# DMB-4770-4-Analog_4-DAC.net
KiCad netlist of a schematic drawn in EAGLE
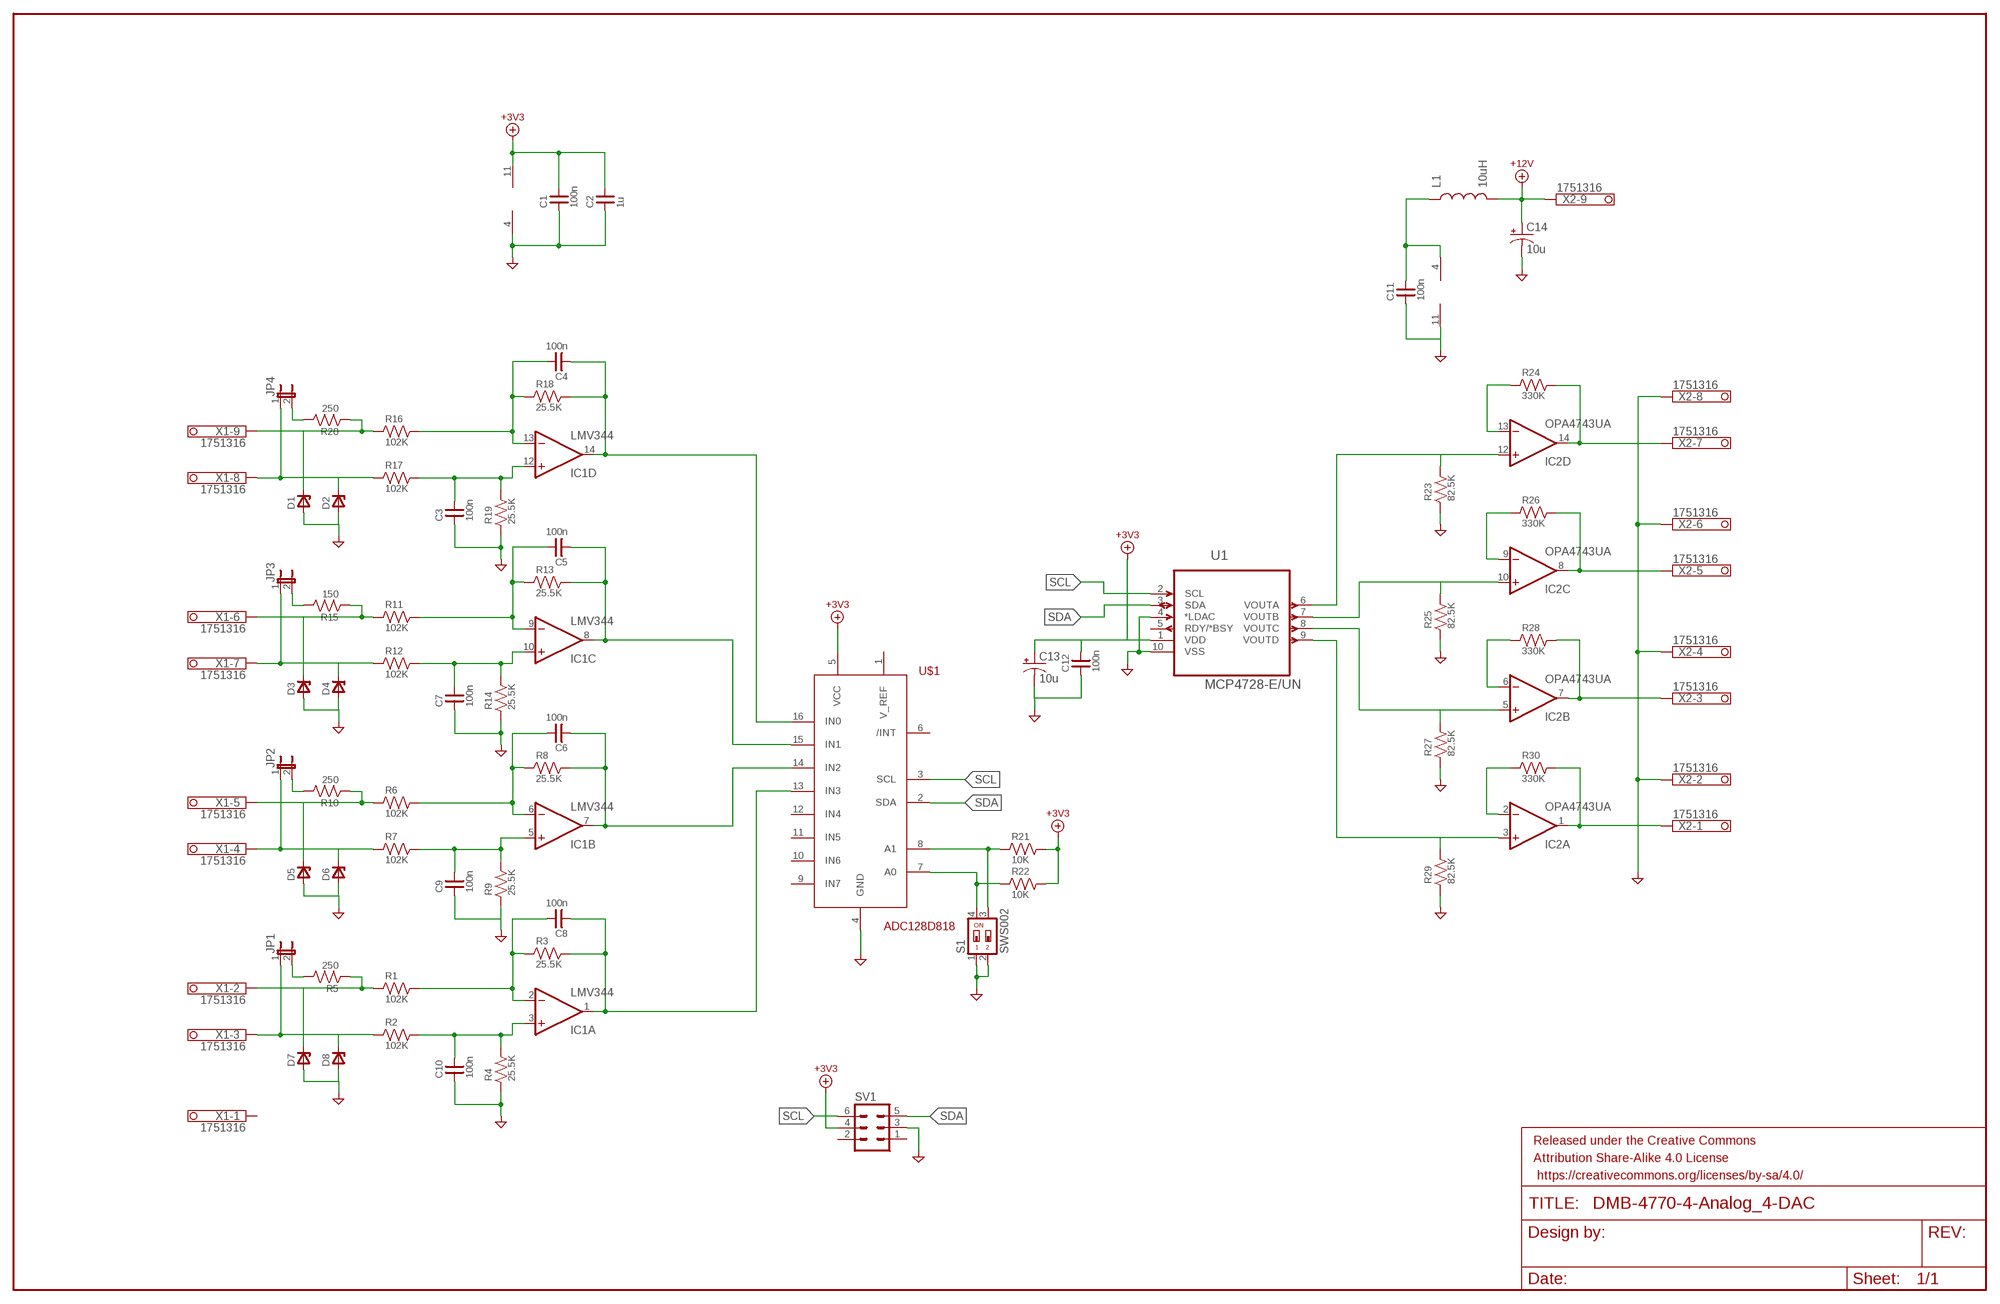
[diagram p0: schematic, sheet 1]

(export (version "E")
  (design (tool "Eeschema 10.0.6"))
  (components
    (comp (ref "C1")
      (value "100n")
      (footprint "eagle-import:C0805")
      (libsource (lib "eagle-import") (part "C0805"))
    )
    (comp (ref "C2")
      (value "1u")
      (footprint "eagle-import:C0805")
      (libsource (lib "eagle-import") (part "C0805"))
    )
    (comp (ref "C3")
      (value "100n")
      (footprint "eagle-import:C0805")
      (libsource (lib "eagle-import") (part "C0805"))
    )
    (comp (ref "C4")
      (value "100n")
      (footprint "eagle-import:C0805")
      (libsource (lib "eagle-import") (part "C0805"))
    )
    (comp (ref "C5")
      (value "100n")
      (footprint "eagle-import:C0805")
      (libsource (lib "eagle-import") (part "C0805"))
    )
    (comp (ref "C6")
      (value "100n")
      (footprint "eagle-import:C0805")
      (libsource (lib "eagle-import") (part "C0805"))
    )
    (comp (ref "C7")
      (value "100n")
      (footprint "eagle-import:C0805")
      (libsource (lib "eagle-import") (part "C0805"))
    )
    (comp (ref "C8")
      (value "100n")
      (footprint "eagle-import:C0805")
      (libsource (lib "eagle-import") (part "C0805"))
    )
    (comp (ref "C9")
      (value "100n")
      (footprint "eagle-import:C0805")
      (libsource (lib "eagle-import") (part "C0805"))
    )
    (comp (ref "C10")
      (value "100n")
      (footprint "eagle-import:C0805")
      (libsource (lib "eagle-import") (part "C0805"))
    )
    (comp (ref "C11")
      (value "100n")
      (footprint "eagle-import:C0805")
      (libsource (lib "eagle-import") (part "C0805"))
    )
    (comp (ref "C12")
      (value "100n")
      (footprint "eagle-import:C0805")
      (libsource (lib "eagle-import") (part "C0805"))
    )
    (comp (ref "C13")
      (value "10u")
      (footprint "eagle-import:EIA3216")
      (libsource (lib "eagle-import") (part "CAP_POL1206"))
    )
    (comp (ref "C14")
      (value "10u")
      (footprint "eagle-import:EIA3216")
      (libsource (lib "eagle-import") (part "CAP_POL1206"))
    )
    (comp (ref "D1")
      (value "DZS")
      (footprint "eagle-import:DMINIMELF")
      (libsource (lib "eagle-import") (part "DZS"))
    )
    (comp (ref "D2")
      (value "DZS")
      (footprint "eagle-import:DMINIMELF")
      (libsource (lib "eagle-import") (part "DZS"))
    )
    (comp (ref "D3")
      (value "DZS")
      (footprint "eagle-import:DMINIMELF")
      (libsource (lib "eagle-import") (part "DZS"))
    )
    (comp (ref "D4")
      (value "DZS")
      (footprint "eagle-import:DMINIMELF")
      (libsource (lib "eagle-import") (part "DZS"))
    )
    (comp (ref "D5")
      (value "DZS")
      (footprint "eagle-import:DMINIMELF")
      (libsource (lib "eagle-import") (part "DZS"))
    )
    (comp (ref "D6")
      (value "DZS")
      (footprint "eagle-import:DMINIMELF")
      (libsource (lib "eagle-import") (part "DZS"))
    )
    (comp (ref "D7")
      (value "DZS")
      (footprint "eagle-import:DMINIMELF")
      (libsource (lib "eagle-import") (part "DZS"))
    )
    (comp (ref "D8")
      (value "DZS")
      (footprint "eagle-import:DMINIMELF")
      (libsource (lib "eagle-import") (part "DZS"))
    )
    (comp (ref "FRAME1")
      (value "FRAME-LEDGER")
      (footprint "eagle-import:CREATIVE_COMMONS")
      (libsource (lib "eagle-import") (part "FRAME-LEDGER"))
    )
    (comp (ref "IC1")
      (value "LMV344")
      (footprint "eagle-import:SO14")
      (libsource (lib "eagle-import") (part "LMV324?M"))
    )
    (comp (ref "IC2")
      (value "OPA4743UA")
      (footprint "eagle-import:SO14")
      (libsource (lib "eagle-import") (part "OPA4743UA"))
    )
    (comp (ref "JP1")
      (value "JP1E")
      (footprint "eagle-import:JP1")
      (libsource (lib "eagle-import") (part "JP1E"))
    )
    (comp (ref "JP2")
      (value "JP1E")
      (footprint "eagle-import:JP1")
      (libsource (lib "eagle-import") (part "JP1E"))
    )
    (comp (ref "JP3")
      (value "JP1E")
      (footprint "eagle-import:JP1")
      (libsource (lib "eagle-import") (part "JP1E"))
    )
    (comp (ref "JP4")
      (value "JP1E")
      (footprint "eagle-import:JP1")
      (libsource (lib "eagle-import") (part "JP1E"))
    )
    (comp (ref "L1")
      (value "10uH")
      (footprint "eagle-import:0805")
      (libsource (lib "eagle-import") (part "INDUCTOR0805"))
    )
    (comp (ref "R1")
      (value "102K")
      (footprint "eagle-import:R0805")
      (libsource (lib "eagle-import") (part "RU0805"))
    )
    (comp (ref "R2")
      (value "102K")
      (footprint "eagle-import:R0805")
      (libsource (lib "eagle-import") (part "RU0805"))
    )
    (comp (ref "R3")
      (value "25.5K")
      (footprint "eagle-import:R0805")
      (libsource (lib "eagle-import") (part "RU0805"))
    )
    (comp (ref "R4")
      (value "25.5K")
      (footprint "eagle-import:R0805")
      (libsource (lib "eagle-import") (part "RU0805"))
    )
    (comp (ref "R5")
      (value "250")
      (footprint "eagle-import:R0805")
      (libsource (lib "eagle-import") (part "RU0805"))
    )
    (comp (ref "R6")
      (value "102K")
      (footprint "eagle-import:R0805")
      (libsource (lib "eagle-import") (part "RU0805"))
    )
    (comp (ref "R7")
      (value "102K")
      (footprint "eagle-import:R0805")
      (libsource (lib "eagle-import") (part "RU0805"))
    )
    (comp (ref "R8")
      (value "25.5K")
      (footprint "eagle-import:R0805")
      (libsource (lib "eagle-import") (part "RU0805"))
    )
    (comp (ref "R9")
      (value "25.5K")
      (footprint "eagle-import:R0805")
      (libsource (lib "eagle-import") (part "RU0805"))
    )
    (comp (ref "R10")
      (value "250")
      (footprint "eagle-import:R0805")
      (libsource (lib "eagle-import") (part "RU0805"))
    )
    (comp (ref "R11")
      (value "102K")
      (footprint "eagle-import:R0805")
      (libsource (lib "eagle-import") (part "RU0805"))
    )
    (comp (ref "R12")
      (value "102K")
      (footprint "eagle-import:R0805")
      (libsource (lib "eagle-import") (part "RU0805"))
    )
    (comp (ref "R13")
      (value "25.5K")
      (footprint "eagle-import:R0805")
      (libsource (lib "eagle-import") (part "RU0805"))
    )
    (comp (ref "R14")
      (value "25.5K")
      (footprint "eagle-import:R0805")
      (libsource (lib "eagle-import") (part "RU0805"))
    )
    (comp (ref "R15")
      (value "150")
      (footprint "eagle-import:R0805")
      (libsource (lib "eagle-import") (part "RU0805"))
    )
    (comp (ref "R16")
      (value "102K")
      (footprint "eagle-import:R0805")
      (libsource (lib "eagle-import") (part "RU0805"))
    )
    (comp (ref "R17")
      (value "102K")
      (footprint "eagle-import:R0805")
      (libsource (lib "eagle-import") (part "RU0805"))
    )
    (comp (ref "R18")
      (value "25.5K")
      (footprint "eagle-import:R0805")
      (libsource (lib "eagle-import") (part "RU0805"))
    )
    (comp (ref "R19")
      (value "25.5K")
      (footprint "eagle-import:R0805")
      (libsource (lib "eagle-import") (part "RU0805"))
    )
    (comp (ref "R20")
      (value "250")
      (footprint "eagle-import:R0805")
      (libsource (lib "eagle-import") (part "RU0805"))
    )
    (comp (ref "R21")
      (value "10K")
      (footprint "eagle-import:R0805")
      (libsource (lib "eagle-import") (part "RU0805"))
    )
    (comp (ref "R22")
      (value "10K")
      (footprint "eagle-import:R0805")
      (libsource (lib "eagle-import") (part "RU0805"))
    )
    (comp (ref "R23")
      (value "82.5K")
      (footprint "eagle-import:R0805")
      (libsource (lib "eagle-import") (part "RU0805"))
    )
    (comp (ref "R24")
      (value "330K")
      (footprint "eagle-import:R0805")
      (libsource (lib "eagle-import") (part "RU0805"))
    )
    (comp (ref "R25")
      (value "82.5K")
      (footprint "eagle-import:R0805")
      (libsource (lib "eagle-import") (part "RU0805"))
    )
    (comp (ref "R26")
      (value "330K")
      (footprint "eagle-import:R0805")
      (libsource (lib "eagle-import") (part "RU0805"))
    )
    (comp (ref "R27")
      (value "82.5K")
      (footprint "eagle-import:R0805")
      (libsource (lib "eagle-import") (part "RU0805"))
    )
    (comp (ref "R28")
      (value "330K")
      (footprint "eagle-import:R0805")
      (libsource (lib "eagle-import") (part "RU0805"))
    )
    (comp (ref "R29")
      (value "82.5K")
      (footprint "eagle-import:R0805")
      (libsource (lib "eagle-import") (part "RU0805"))
    )
    (comp (ref "R30")
      (value "330K")
      (footprint "eagle-import:R0805")
      (libsource (lib "eagle-import") (part "RU0805"))
    )
    (comp (ref "S1")
      (value "SWS002")
      (footprint "eagle-import:SMS-002")
      (libsource (lib "eagle-import") (part "SWS002"))
    )
    (comp (ref "SV1")
      (value "ML6")
      (footprint "eagle-import:ML6")
      (libsource (lib "eagle-import") (part "ML6"))
    )
    (comp (ref "U$1")
      (value "ADC128D818")
      (footprint "eagle-import:SSOP16")
      (libsource (lib "eagle-import") (part "ADC128D818"))
    )
    (comp (ref "U1")
      (value "MCP4728-E/UN")
      (footprint "eagle-import:SOP50P490X110-10N")
      (libsource (lib "eagle-import") (part "MCP4728-E/UN"))
    )
    (comp (ref "X1")
      (value "1751316")
      (footprint "eagle-import:1751316")
      (libsource (lib "eagle-import") (part "1751316"))
    )
    (comp (ref "X2")
      (value "1751316")
      (footprint "eagle-import:1751316")
      (libsource (lib "eagle-import") (part "1751316"))
    )
  )
  (nets
    (net (code "1") (name "Net-(IC1A-+IN)") (class "Default")
      (node (ref "C10") (pin "2") (pinfunction "2_2") (pintype "passive"))
      (node (ref "IC1") (pin "3") (pinfunction "+IN_3") (pintype "input"))
      (node (ref "R2") (pin "2") (pinfunction "2_2") (pintype "passive"))
      (node (ref "R4") (pin "2") (pinfunction "2_2") (pintype "passive"))
    )
    (net (code "2") (name "Net-(IC1A--IN)") (class "Default")
      (node (ref "C8") (pin "2") (pinfunction "2_2") (pintype "passive"))
      (node (ref "IC1") (pin "2") (pinfunction "-IN_2") (pintype "input"))
      (node (ref "R1") (pin "2") (pinfunction "2_2") (pintype "passive"))
      (node (ref "R3") (pin "1") (pinfunction "1_1") (pintype "passive"))
    )
    (net (code "3") (name "Net-(IC1A-OUT)") (class "Default")
      (node (ref "C8") (pin "1") (pinfunction "1_1") (pintype "passive"))
      (node (ref "IC1") (pin "1") (pinfunction "OUT_1") (pintype "output"))
      (node (ref "R3") (pin "2") (pinfunction "2_2") (pintype "passive"))
      (node (ref "U$1") (pin "13") (pinfunction "IN3_13") (pintype "input"))
    )
    (net (code "4") (name "Net-(IC1B-+IN)") (class "Default")
      (node (ref "C9") (pin "2") (pinfunction "2_2") (pintype "passive"))
      (node (ref "IC1") (pin "5") (pinfunction "+IN_5") (pintype "input"))
      (node (ref "R7") (pin "2") (pinfunction "2_2") (pintype "passive"))
      (node (ref "R9") (pin "2") (pinfunction "2_2") (pintype "passive"))
    )
    (net (code "5") (name "Net-(IC1B--IN)") (class "Default")
      (node (ref "C6") (pin "2") (pinfunction "2_2") (pintype "passive"))
      (node (ref "IC1") (pin "6") (pinfunction "-IN_6") (pintype "input"))
      (node (ref "R6") (pin "2") (pinfunction "2_2") (pintype "passive"))
      (node (ref "R8") (pin "1") (pinfunction "1_1") (pintype "passive"))
    )
    (net (code "6") (name "Net-(IC1B-OUT)") (class "Default")
      (node (ref "C6") (pin "1") (pinfunction "1_1") (pintype "passive"))
      (node (ref "IC1") (pin "7") (pinfunction "OUT_7") (pintype "output"))
      (node (ref "R8") (pin "2") (pinfunction "2_2") (pintype "passive"))
      (node (ref "U$1") (pin "14") (pinfunction "IN2_14") (pintype "input"))
    )
    (net (code "7") (name "Net-(IC1C-+IN)") (class "Default")
      (node (ref "C7") (pin "2") (pinfunction "2_2") (pintype "passive"))
      (node (ref "IC1") (pin "10") (pinfunction "+IN_10") (pintype "input"))
      (node (ref "R12") (pin "2") (pinfunction "2_2") (pintype "passive"))
      (node (ref "R14") (pin "2") (pinfunction "2_2") (pintype "passive"))
    )
    (net (code "8") (name "Net-(IC1C--IN)") (class "Default")
      (node (ref "C5") (pin "2") (pinfunction "2_2") (pintype "passive"))
      (node (ref "IC1") (pin "9") (pinfunction "-IN_9") (pintype "input"))
      (node (ref "R11") (pin "2") (pinfunction "2_2") (pintype "passive"))
      (node (ref "R13") (pin "1") (pinfunction "1_1") (pintype "passive"))
    )
    (net (code "9") (name "Net-(IC1C-OUT)") (class "Default")
      (node (ref "C5") (pin "1") (pinfunction "1_1") (pintype "passive"))
      (node (ref "IC1") (pin "8") (pinfunction "OUT_8") (pintype "output"))
      (node (ref "R13") (pin "2") (pinfunction "2_2") (pintype "passive"))
      (node (ref "U$1") (pin "15") (pinfunction "IN1_15") (pintype "input"))
    )
    (net (code "10") (name "Net-(IC1D-+IN)") (class "Default")
      (node (ref "C3") (pin "2") (pinfunction "2_2") (pintype "passive"))
      (node (ref "IC1") (pin "12") (pinfunction "+IN_12") (pintype "input"))
      (node (ref "R17") (pin "2") (pinfunction "2_2") (pintype "passive"))
      (node (ref "R19") (pin "2") (pinfunction "2_2") (pintype "passive"))
    )
    (net (code "11") (name "Net-(IC1D--IN)") (class "Default")
      (node (ref "C4") (pin "2") (pinfunction "2_2") (pintype "passive"))
      (node (ref "IC1") (pin "13") (pinfunction "-IN_13") (pintype "input"))
      (node (ref "R16") (pin "2") (pinfunction "2_2") (pintype "passive"))
      (node (ref "R18") (pin "1") (pinfunction "1_1") (pintype "passive"))
    )
    (net (code "12") (name "Net-(IC1D-OUT)") (class "Default")
      (node (ref "C4") (pin "1") (pinfunction "1_1") (pintype "passive"))
      (node (ref "IC1") (pin "14") (pinfunction "OUT_14") (pintype "output"))
      (node (ref "R18") (pin "2") (pinfunction "2_2") (pintype "passive"))
      (node (ref "U$1") (pin "16") (pinfunction "IN0_16") (pintype "input"))
    )
    (net (code "13") (name "Net-(IC2A-+IN)") (class "Default")
      (node (ref "IC2") (pin "3") (pinfunction "+IN_3") (pintype "input"))
      (node (ref "R29") (pin "2") (pinfunction "2_2") (pintype "passive"))
      (node (ref "U1") (pin "9") (pinfunction "VOUTD_9") (pintype "output"))
    )
    (net (code "14") (name "Net-(IC2A--IN)") (class "Default")
      (node (ref "IC2") (pin "2") (pinfunction "-IN_2") (pintype "input"))
      (node (ref "R30") (pin "1") (pinfunction "1_1") (pintype "passive"))
    )
    (net (code "15") (name "Net-(IC2A-OUT)") (class "Default")
      (node (ref "IC2") (pin "1") (pinfunction "OUT_1") (pintype "output"))
      (node (ref "R30") (pin "2") (pinfunction "2_2") (pintype "passive"))
      (node (ref "X2") (pin "1") (pinfunction "K_1") (pintype "passive"))
    )
    (net (code "16") (name "Net-(IC2B-+IN)") (class "Default")
      (node (ref "IC2") (pin "5") (pinfunction "+IN_5") (pintype "input"))
      (node (ref "R27") (pin "2") (pinfunction "2_2") (pintype "passive"))
      (node (ref "U1") (pin "8") (pinfunction "VOUTC_8") (pintype "output"))
    )
    (net (code "17") (name "Net-(IC2B--IN)") (class "Default")
      (node (ref "IC2") (pin "6") (pinfunction "-IN_6") (pintype "input"))
      (node (ref "R28") (pin "1") (pinfunction "1_1") (pintype "passive"))
    )
    (net (code "18") (name "Net-(IC2B-OUT)") (class "Default")
      (node (ref "IC2") (pin "7") (pinfunction "OUT_7") (pintype "output"))
      (node (ref "R28") (pin "2") (pinfunction "2_2") (pintype "passive"))
      (node (ref "X2") (pin "3") (pinfunction "K_3") (pintype "passive"))
    )
    (net (code "19") (name "Net-(IC2C-+IN)") (class "Default")
      (node (ref "IC2") (pin "10") (pinfunction "+IN_10") (pintype "input"))
      (node (ref "R25") (pin "2") (pinfunction "2_2") (pintype "passive"))
      (node (ref "U1") (pin "7") (pinfunction "VOUTB_7") (pintype "output"))
    )
    (net (code "20") (name "Net-(IC2C--IN)") (class "Default")
      (node (ref "IC2") (pin "9") (pinfunction "-IN_9") (pintype "input"))
      (node (ref "R26") (pin "1") (pinfunction "1_1") (pintype "passive"))
    )
    (net (code "21") (name "Net-(IC2C-OUT)") (class "Default")
      (node (ref "IC2") (pin "8") (pinfunction "OUT_8") (pintype "output"))
      (node (ref "R26") (pin "2") (pinfunction "2_2") (pintype "passive"))
      (node (ref "X2") (pin "5") (pinfunction "K_5") (pintype "passive"))
    )
    (net (code "22") (name "Net-(IC2D-+IN)") (class "Default")
      (node (ref "IC2") (pin "12") (pinfunction "+IN_12") (pintype "input"))
      (node (ref "R23") (pin "2") (pinfunction "2_2") (pintype "passive"))
      (node (ref "U1") (pin "6") (pinfunction "VOUTA_6") (pintype "output"))
    )
    (net (code "23") (name "Net-(IC2D--IN)") (class "Default")
      (node (ref "IC2") (pin "13") (pinfunction "-IN_13") (pintype "input"))
      (node (ref "R24") (pin "1") (pinfunction "1_1") (pintype "passive"))
    )
    (net (code "24") (name "Net-(IC2D-OUT)") (class "Default")
      (node (ref "IC2") (pin "14") (pinfunction "OUT_14") (pintype "output"))
      (node (ref "R24") (pin "2") (pinfunction "2_2") (pintype "passive"))
      (node (ref "X2") (pin "7") (pinfunction "K_7") (pintype "passive"))
    )
    (net (code "25") (name "Net-(IC2E-V+)") (class "Default")
      (node (ref "C11") (pin "2") (pinfunction "2_2") (pintype "passive"))
      (node (ref "IC2") (pin "4") (pinfunction "V+_4") (pintype "power_in"))
      (node (ref "L1") (pin "1") (pinfunction "1_1") (pintype "passive"))
    )
    (net (code "26") (name "Net-(JP1-Pad2)") (class "Default")
      (node (ref "JP1") (pin "2") (pinfunction "2_2") (pintype "passive"))
      (node (ref "R5") (pin "2") (pinfunction "2_2") (pintype "passive"))
    )
    (net (code "27") (name "Net-(JP2-Pad2)") (class "Default")
      (node (ref "JP2") (pin "2") (pinfunction "2_2") (pintype "passive"))
      (node (ref "R10") (pin "2") (pinfunction "2_2") (pintype "passive"))
    )
    (net (code "28") (name "Net-(JP3-Pad2)") (class "Default")
      (node (ref "JP3") (pin "2") (pinfunction "2_2") (pintype "passive"))
      (node (ref "R15") (pin "2") (pinfunction "2_2") (pintype "passive"))
    )
    (net (code "29") (name "Net-(JP4-Pad2)") (class "Default")
      (node (ref "JP4") (pin "2") (pinfunction "2_2") (pintype "passive"))
      (node (ref "R20") (pin "2") (pinfunction "2_2") (pintype "passive"))
    )
    (net (code "30") (name "Net-(U$1-A0)") (class "Default")
      (node (ref "R22") (pin "1") (pinfunction "1_1") (pintype "passive"))
      (node (ref "S1") (pin "4") (pinfunction "4_4") (pintype "passive"))
      (node (ref "U$1") (pin "7") (pinfunction "A0_7") (pintype "input"))
    )
    (net (code "31") (name "Net-(U$1-A1)") (class "Default")
      (node (ref "R21") (pin "1") (pinfunction "1_1") (pintype "passive"))
      (node (ref "S1") (pin "3") (pinfunction "3_3") (pintype "passive"))
      (node (ref "U$1") (pin "8") (pinfunction "A1_8") (pintype "input"))
    )
    (net (code "32") (name "Net-(X1B-K)") (class "Default")
      (node (ref "R1") (pin "1") (pinfunction "1_1") (pintype "passive"))
      (node (ref "R5") (pin "1") (pinfunction "1_1") (pintype "passive"))
      (node (ref "X1") (pin "2") (pinfunction "K_2") (pintype "passive"))
    )
    (net (code "33") (name "Net-(X1C-K)") (class "Default")
      (node (ref "JP1") (pin "1") (pinfunction "1_1") (pintype "passive"))
      (node (ref "R2") (pin "1") (pinfunction "1_1") (pintype "passive"))
      (node (ref "X1") (pin "3") (pinfunction "K_3") (pintype "passive"))
    )
    (net (code "34") (name "Net-(X1D-K)") (class "Default")
      (node (ref "JP2") (pin "1") (pinfunction "1_1") (pintype "passive"))
      (node (ref "R7") (pin "1") (pinfunction "1_1") (pintype "passive"))
      (node (ref "X1") (pin "4") (pinfunction "K_4") (pintype "passive"))
    )
    (net (code "35") (name "Net-(X1E-K)") (class "Default")
      (node (ref "R10") (pin "1") (pinfunction "1_1") (pintype "passive"))
      (node (ref "R6") (pin "1") (pinfunction "1_1") (pintype "passive"))
      (node (ref "X1") (pin "5") (pinfunction "K_5") (pintype "passive"))
    )
    (net (code "36") (name "Net-(X1F-K)") (class "Default")
      (node (ref "R11") (pin "1") (pinfunction "1_1") (pintype "passive"))
      (node (ref "R15") (pin "1") (pinfunction "1_1") (pintype "passive"))
      (node (ref "X1") (pin "6") (pinfunction "K_6") (pintype "passive"))
    )
    (net (code "37") (name "Net-(X1G-K)") (class "Default")
      (node (ref "JP3") (pin "1") (pinfunction "1_1") (pintype "passive"))
      (node (ref "R12") (pin "1") (pinfunction "1_1") (pintype "passive"))
      (node (ref "X1") (pin "7") (pinfunction "K_7") (pintype "passive"))
    )
    (net (code "38") (name "Net-(X1H-K)") (class "Default")
      (node (ref "D2") (pin "C") (pinfunction "C_C") (pintype "passive"))
      (node (ref "JP4") (pin "1") (pinfunction "1_1") (pintype "passive"))
      (node (ref "R17") (pin "1") (pinfunction "1_1") (pintype "passive"))
      (node (ref "X1") (pin "8") (pinfunction "K_8") (pintype "passive"))
    )
    (net (code "39") (name "Net-(X1I-K)") (class "Default")
      (node (ref "D1") (pin "C") (pinfunction "C_C") (pintype "passive"))
      (node (ref "R16") (pin "1") (pinfunction "1_1") (pintype "passive"))
      (node (ref "R20") (pin "1") (pinfunction "1_1") (pintype "passive"))
      (node (ref "X1") (pin "9") (pinfunction "K_9") (pintype "passive"))
    )
    (net (code "40") (name "SCL") (class "Default")
      (node (ref "SV1") (pin "6") (pinfunction "6_6") (pintype "passive"))
    )
    (net (code "41") (name "SDA") (class "Default")
      (node (ref "SV1") (pin "5") (pinfunction "5_5") (pintype "passive"))
    )
    (net (code "42") (name "V+3V3") (class "Default")
      (node (ref "C1") (pin "2") (pinfunction "2_2") (pintype "passive"))
      (node (ref "C12") (pin "2") (pinfunction "2_2") (pintype "passive"))
      (node (ref "C13") (pin "A") (pinfunction "+_A") (pintype "passive"))
      (node (ref "C2") (pin "2") (pinfunction "2_2") (pintype "passive"))
      (node (ref "IC1") (pin "11") (pinfunction "V-_11") (pintype "power_in"))
      (node (ref "R21") (pin "2") (pinfunction "2_2") (pintype "passive"))
      (node (ref "R22") (pin "2") (pinfunction "2_2") (pintype "passive"))
      (node (ref "SV1") (pin "4") (pinfunction "4_4") (pintype "passive"))
      (node (ref "U$1") (pin "5") (pinfunction "VCC_5") (pintype "power_in"))
      (node (ref "U1") (pin "1") (pinfunction "VDD_1") (pintype "power_in"))
    )
    (net (code "43") (name "V+12V") (class "Default")
      (node (ref "C14") (pin "A") (pinfunction "+_A") (pintype "passive"))
      (node (ref "L1") (pin "2") (pinfunction "2_2") (pintype "passive"))
      (node (ref "X2") (pin "9") (pinfunction "K_9") (pintype "passive"))
    )
    (net (code "44") (name "VDG") (class "Default")
      (node (ref "C1") (pin "1") (pinfunction "1_1") (pintype "passive"))
      (node (ref "C10") (pin "1") (pinfunction "1_1") (pintype "passive"))
      (node (ref "C11") (pin "1") (pinfunction "1_1") (pintype "passive"))
      (node (ref "C12") (pin "1") (pinfunction "1_1") (pintype "passive"))
      (node (ref "C13") (pin "C") (pinfunction "-_C") (pintype "passive"))
      (node (ref "C14") (pin "C") (pinfunction "-_C") (pintype "passive"))
      (node (ref "C2") (pin "1") (pinfunction "1_1") (pintype "passive"))
      (node (ref "C3") (pin "1") (pinfunction "1_1") (pintype "passive"))
      (node (ref "C7") (pin "1") (pinfunction "1_1") (pintype "passive"))
      (node (ref "C9") (pin "1") (pinfunction "1_1") (pintype "passive"))
      (node (ref "D1") (pin "A") (pinfunction "A_A") (pintype "passive"))
      (node (ref "D2") (pin "A") (pinfunction "A_A") (pintype "passive"))
      (node (ref "D3") (pin "A") (pinfunction "A_A") (pintype "passive"))
      (node (ref "D4") (pin "A") (pinfunction "A_A") (pintype "passive"))
      (node (ref "D5") (pin "A") (pinfunction "A_A") (pintype "passive"))
      (node (ref "D6") (pin "A") (pinfunction "A_A") (pintype "passive"))
      (node (ref "D7") (pin "A") (pinfunction "A_A") (pintype "passive"))
      (node (ref "D8") (pin "A") (pinfunction "A_A") (pintype "passive"))
      (node (ref "IC1") (pin "4") (pinfunction "V+_4") (pintype "power_in"))
      (node (ref "IC2") (pin "11") (pinfunction "V-_11") (pintype "power_in"))
      (node (ref "R14") (pin "1") (pinfunction "1_1") (pintype "passive"))
      (node (ref "R19") (pin "1") (pinfunction "1_1") (pintype "passive"))
      (node (ref "R23") (pin "1") (pinfunction "1_1") (pintype "passive"))
      (node (ref "R25") (pin "1") (pinfunction "1_1") (pintype "passive"))
      (node (ref "R27") (pin "1") (pinfunction "1_1") (pintype "passive"))
      (node (ref "R29") (pin "1") (pinfunction "1_1") (pintype "passive"))
      (node (ref "R4") (pin "1") (pinfunction "1_1") (pintype "passive"))
      (node (ref "R9") (pin "1") (pinfunction "1_1") (pintype "passive"))
      (node (ref "S1") (pin "1") (pinfunction "1_1") (pintype "passive"))
      (node (ref "S1") (pin "2") (pinfunction "2_2") (pintype "passive"))
      (node (ref "SV1") (pin "3") (pinfunction "3_3") (pintype "passive"))
      (node (ref "U$1") (pin "4") (pinfunction "GND_4") (pintype "power_in"))
      (node (ref "U1") (pin "10") (pinfunction "VSS_10") (pintype "power_in"))
      (node (ref "U1") (pin "4") (pinfunction "*LDAC_4") (pintype "input"))
      (node (ref "X2") (pin "2") (pinfunction "K_2") (pintype "passive"))
      (node (ref "X2") (pin "4") (pinfunction "K_4") (pintype "passive"))
      (node (ref "X2") (pin "6") (pinfunction "K_6") (pintype "passive"))
      (node (ref "X2") (pin "8") (pinfunction "K_8") (pintype "passive"))
    )
    (net (code "45") (name "unconnected-(D3-PadC)") (class "Default")
      (node (ref "D3") (pin "C") (pinfunction "C_C") (pintype "passive"))
    )
    (net (code "46") (name "unconnected-(D4-PadC)") (class "Default")
      (node (ref "D4") (pin "C") (pinfunction "C_C") (pintype "passive"))
    )
    (net (code "47") (name "unconnected-(D5-PadC)") (class "Default")
      (node (ref "D5") (pin "C") (pinfunction "C_C") (pintype "passive"))
    )
    (net (code "48") (name "unconnected-(D6-PadC)") (class "Default")
      (node (ref "D6") (pin "C") (pinfunction "C_C") (pintype "passive"))
    )
    (net (code "49") (name "unconnected-(D7-PadC)") (class "Default")
      (node (ref "D7") (pin "C") (pinfunction "C_C") (pintype "passive"))
    )
    (net (code "50") (name "unconnected-(D8-PadC)") (class "Default")
      (node (ref "D8") (pin "C") (pinfunction "C_C") (pintype "passive"))
    )
    (net (code "51") (name "unconnected-(SV1-Pad1)") (class "Default")
      (node (ref "SV1") (pin "1") (pinfunction "1_1") (pintype "passive"))
    )
    (net (code "52") (name "unconnected-(SV1-Pad2)") (class "Default")
      (node (ref "SV1") (pin "2") (pinfunction "2_2") (pintype "passive"))
    )
    (net (code "53") (name "unconnected-(U$1-IN4-Pad12)") (class "Default")
      (node (ref "U$1") (pin "12") (pinfunction "IN4_12") (pintype "input"))
    )
    (net (code "54") (name "unconnected-(U$1-IN5-Pad11)") (class "Default")
      (node (ref "U$1") (pin "11") (pinfunction "IN5_11") (pintype "input"))
    )
    (net (code "55") (name "unconnected-(U$1-IN6-Pad10)") (class "Default")
      (node (ref "U$1") (pin "10") (pinfunction "IN6_10") (pintype "input"))
    )
    (net (code "56") (name "unconnected-(U$1-IN7-Pad9)") (class "Default")
      (node (ref "U$1") (pin "9") (pinfunction "IN7_9") (pintype "input"))
    )
    (net (code "57") (name "unconnected-(U$1-SCL-Pad3)") (class "Default")
      (node (ref "U$1") (pin "3") (pinfunction "SCL_3") (pintype "input"))
    )
    (net (code "58") (name "unconnected-(U$1-SDA-Pad2)") (class "Default")
      (node (ref "U$1") (pin "2") (pinfunction "SDA_2") (pintype "bidirectional"))
    )
    (net (code "59") (name "unconnected-(U$1-V_REF-Pad1)") (class "Default")
      (node (ref "U$1") (pin "1") (pinfunction "V_REF_1") (pintype "input"))
    )
    (net (code "60") (name "unconnected-(U$1-{slash}INT-Pad6)") (class "Default")
      (node (ref "U$1") (pin "6") (pinfunction "/INT_6") (pintype "output"))
    )
    (net (code "61") (name "unconnected-(U1-RDY{slash}*BSY-Pad5)") (class "Default")
      (node (ref "U1") (pin "5") (pinfunction "RDY/*BSY_5") (pintype "output"))
    )
    (net (code "62") (name "unconnected-(U1-SCL-Pad2)") (class "Default")
      (node (ref "U1") (pin "2") (pinfunction "SCL_2") (pintype "input"))
    )
    (net (code "63") (name "unconnected-(U1-SDA-Pad3)") (class "Default")
      (node (ref "U1") (pin "3") (pinfunction "SDA_3") (pintype "bidirectional"))
    )
    (net (code "64") (name "unconnected-(X1A-K-Pad1)") (class "Default")
      (node (ref "X1") (pin "1") (pinfunction "K_1") (pintype "passive"))
    )
  )
)
